# MP3.net
KiCad netlist of a schematic drawn in Altium Designer
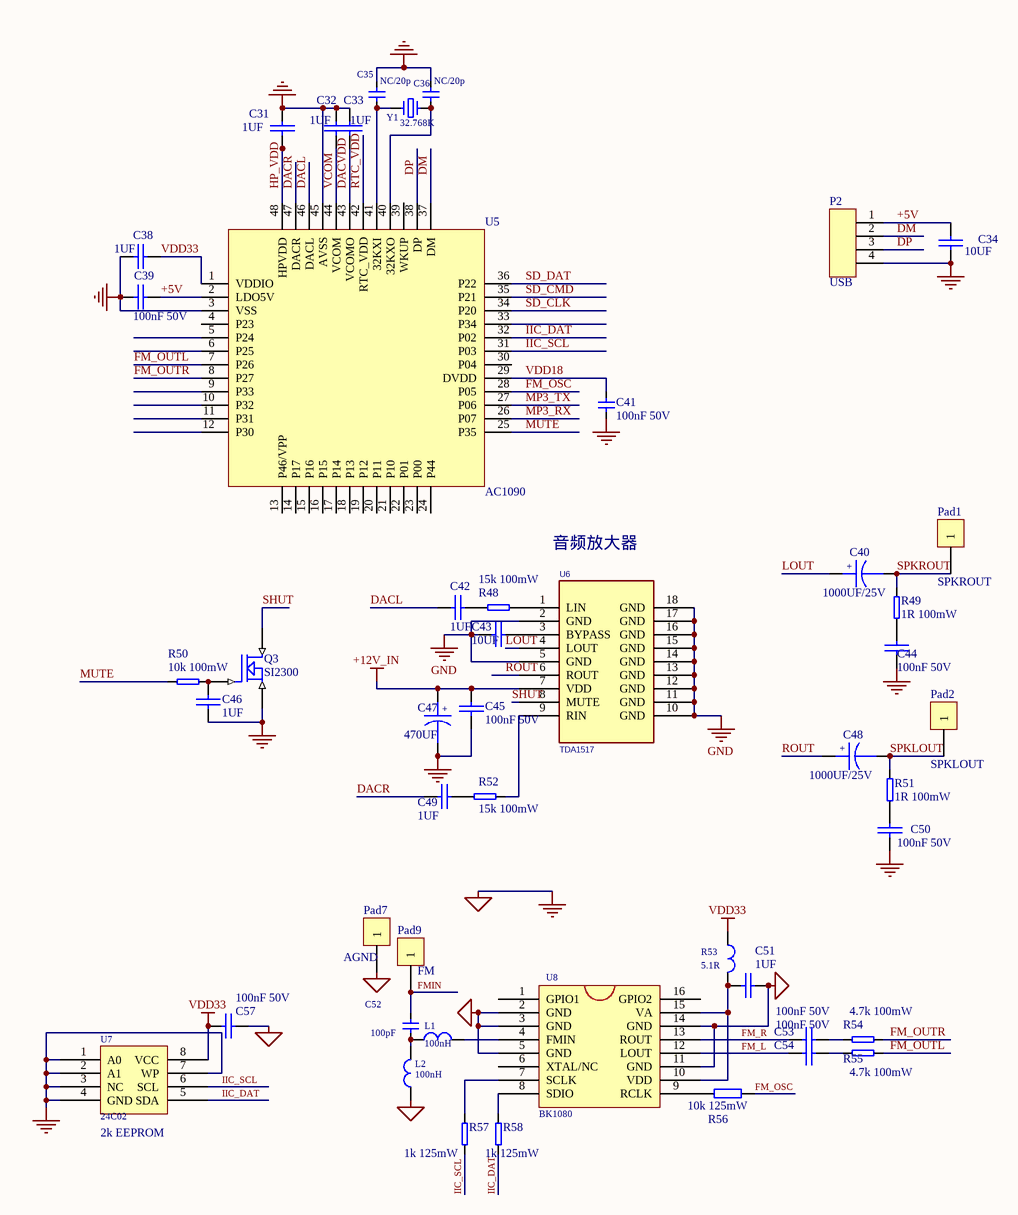
[diagram p0: MP3.SchDoc]

(export (version "E")
  (design (tool "Eeschema 10.0.6"))
  (components
    (comp (ref "C31")
      (value "1UF")
      (footprint "0805")
      (description "Capacitor")
      (libsource (lib "*") (part "CAP"))
    )
    (comp (ref "C32")
      (value "1UF")
      (footprint "0805")
      (description "Capacitor")
      (libsource (lib "*") (part "CAP"))
    )
    (comp (ref "C33")
      (value "1UF")
      (footprint "0805")
      (description "Capacitor")
      (libsource (lib "*") (part "CAP"))
    )
    (comp (ref "C34")
      (value "10UF")
      (footprint "0805")
      (description "Capacitor")
      (libsource (lib "*") (part "CAP"))
    )
    (comp (ref "C35")
      (value "NC/20p")
      (footprint "0603")
      (description "Capacitor")
      (libsource (lib "") (part "CAP_1"))
    )
    (comp (ref "C36")
      (value "NC/20p")
      (footprint "0603")
      (description "Capacitor")
      (libsource (lib "") (part "CAP_1"))
    )
    (comp (ref "C38")
      (value "1UF")
      (footprint "0805")
      (description "Capacitor")
      (libsource (lib "*") (part "CAP"))
    )
    (comp (ref "C39")
      (value "100nF 50V")
      (footprint "0805")
      (description "Capacitor")
      (libsource (lib "") (part "CAP_3"))
    )
    (comp (ref "C40")
      (value "1000UF/25V")
      (footprint "RB.2.4")
      (description "Capacitor")
      (libsource (lib "*") (part "CAPACITOR POL"))
    )
    (comp (ref "C41")
      (value "100nF 50V")
      (footprint "0603")
      (description "Capacitor")
      (libsource (lib "") (part "CAP_1"))
    )
    (comp (ref "C42")
      (value "1UF")
      (footprint "0805")
      (description "Capacitor")
      (libsource (lib "*") (part "CAP"))
    )
    (comp (ref "C43")
      (value "10UF")
      (footprint "0805")
      (description "Capacitor")
      (libsource (lib "*") (part "CAP_1"))
    )
    (comp (ref "C44")
      (value "100nF 50V")
      (footprint "0805")
      (description "Capacitor")
      (libsource (lib "") (part "CAP_3"))
    )
    (comp (ref "C45")
      (value "100nF 50V")
      (footprint "0805")
      (description "Capacitor")
      (libsource (lib "*") (part "CAP"))
    )
    (comp (ref "C46")
      (value "1UF")
      (footprint "0805")
      (description "Capacitor")
      (libsource (lib "*") (part "CAP"))
    )
    (comp (ref "C47")
      (value "470UF")
      (footprint "RB.2/.4")
      (description "Capacitor")
      (libsource (lib "*") (part "CAPACITOR POL"))
    )
    (comp (ref "C48")
      (value "1000UF/25V")
      (footprint "RB.2.4")
      (description "Capacitor")
      (libsource (lib "*") (part "CAPACITOR POL"))
    )
    (comp (ref "C49")
      (value "1UF")
      (footprint "0805")
      (description "Capacitor")
      (libsource (lib "*") (part "CAP"))
    )
    (comp (ref "C50")
      (value "100nF 50V")
      (footprint "0805")
      (description "Capacitor")
      (libsource (lib "") (part "CAP_3"))
    )
    (comp (ref "C51")
      (value "1UF")
      (footprint "0805")
      (description "Capacitor")
      (libsource (lib "*") (part "CAP"))
    )
    (comp (ref "C52")
      (value "100pF")
      (footprint "0603")
      (description "Capacitor")
      (libsource (lib "") (part "CAP_2"))
    )
    (comp (ref "C53")
      (value "100nF 50V")
      (footprint "0805")
      (description "Capacitor")
      (libsource (lib "*") (part "CAP"))
    )
    (comp (ref "C54")
      (value "100nF 50V")
      (footprint "0805")
      (description "Capacitor")
      (libsource (lib "*") (part "CAP"))
    )
    (comp (ref "C57")
      (value "100nF 50V")
      (footprint "0805")
      (description "Capacitor")
      (libsource (lib "*") (part "CAP"))
    )
    (comp (ref "L1") (value "100nH") (footprint "0603") (libsource (lib "*") (part "INDUCTOR")))
    (comp (ref "L2") (value "100nH") (footprint "0603") (libsource (lib "*") (part "INDUCTOR")))
    (comp (ref "P2") (value "USB") (footprint "SIP4") (libsource (lib "whlSCHLIB") (part "CON4")))
    (comp (ref "Pad1")
      (value "SPKROUT")
      (footprint "PAD")
      (description "Connector")
      (libsource (lib "*") (part "CON1"))
    )
    (comp (ref "Pad2")
      (value "SPKLOUT")
      (footprint "PAD")
      (description "Connector")
      (libsource (lib "*") (part "CON1"))
    )
    (comp (ref "Pad7")
      (value "AGND")
      (footprint "PAD")
      (description "Connector")
      (libsource (lib "*") (part "CON1"))
    )
    (comp (ref "Pad9")
      (value "FM")
      (footprint "PAD")
      (description "Connector")
      (libsource (lib "*") (part "CON1"))
    )
    (comp (ref "Q3") (value "SI2300") (footprint "SOT-23") (libsource (lib "*") (part "MOSFET N")))
    (comp (ref "R48") (value "15k 100mW") (footprint "0603") (libsource (lib "*") (part "RES2_1")))
    (comp (ref "R49") (value "1R 100mW") (footprint "0603") (libsource (lib "*") (part "RES2_1")))
    (comp (ref "R50") (value "10k 100mW") (footprint "0603") (libsource (lib "*") (part "RES2_1")))
    (comp (ref "R51") (value "1R 100mW") (footprint "0603") (libsource (lib "*") (part "RES2_1")))
    (comp (ref "R52") (value "15k 100mW") (footprint "0603") (libsource (lib "*") (part "RES2_1")))
    (comp (ref "R53") (value "5.1R") (footprint "0603") (libsource (lib "*") (part "INDUCTOR")))
    (comp (ref "R54") (value "4.7k 100mW") (footprint "0603") (libsource (lib "*") (part "RES2_1")))
    (comp (ref "R55") (value "4.7k 100mW") (footprint "0603") (libsource (lib "*") (part "RES2_1")))
    (comp (ref "R56") (value "10k 125mW") (footprint "0805") (libsource (lib "whlSCHLIB") (part "WHLRES")))
    (comp (ref "R57") (value "1k 125mW") (footprint "0805") (libsource (lib "*") (part "RES2_1")))
    (comp (ref "R58") (value "1k 125mW") (footprint "0805") (libsource (lib "*") (part "RES2_1")))
    (comp (ref "U5") (value "AC1090") (footprint "TQFP48 7X7") (libsource (lib "*") (part "AC1090")))
    (comp (ref "U6") (value "TDA1517") (footprint "DIP18") (libsource (lib "QX-T9") (part "74HC245_0")))
    (comp (ref "U7") (value "24C02") (footprint "SO-8") (libsource (lib "*") (part "EEPROM-8")))
    (comp (ref "U8") (value "BK1080") (footprint "SOP-16") (libsource (lib "*") (part "BK1080")))
    (comp (ref "Y1") (value "32.768K") (footprint "Cry3215") (libsource (lib "*") (part "CRYSTAL")))
  )
  (nets
    (net (code "1") (name "+12V_IN") (class "Default")
      (node (ref "C45") (pin "2") (pinfunction "2_2") (pintype "passive"))
      (node (ref "C47") (pin "1") (pinfunction "1_1") (pintype "passive"))
      (node (ref "U6") (pin "7") (pinfunction "VDD_7") (pintype "passive"))
    )
    (net (code "2") (name "/+5V") (class "Default")
      (node (ref "C34") (pin "1") (pinfunction "1_1") (pintype "passive"))
      (node (ref "C39") (pin "2") (pinfunction "2_2") (pintype "passive"))
      (node (ref "P2") (pin "1") (pintype "passive"))
      (node (ref "U5") (pin "2") (pinfunction "LDO5V_2") (pintype "passive"))
    )
    (net (code "3") (name "/DACL") (class "Default")
      (node (ref "C42") (pin "2") (pinfunction "2_2") (pintype "passive"))
      (node (ref "U5") (pin "46") (pinfunction "DACL_46") (pintype "passive"))
    )
    (net (code "4") (name "/DACR") (class "Default")
      (node (ref "C49") (pin "2") (pinfunction "2_2") (pintype "passive"))
      (node (ref "U5") (pin "47") (pinfunction "DACR_47") (pintype "passive"))
    )
    (net (code "5") (name "/DACVDD") (class "Default")
      (node (ref "C33") (pin "2") (pinfunction "2_2") (pintype "passive"))
      (node (ref "U5") (pin "43") (pinfunction "VCOMO_43") (pintype "passive"))
    )
    (net (code "6") (name "/DM") (class "Default")
      (node (ref "P2") (pin "2") (pintype "passive"))
      (node (ref "U5") (pin "37") (pinfunction "DM_37") (pintype "passive"))
    )
    (net (code "7") (name "/DP") (class "Default")
      (node (ref "P2") (pin "3") (pintype "passive"))
      (node (ref "U5") (pin "38") (pinfunction "DP_38") (pintype "passive"))
    )
    (net (code "8") (name "/FMIN") (class "Default")
      (node (ref "C52") (pin "1") (pinfunction "1_1") (pintype "passive"))
      (node (ref "Pad9") (pin "1") (pinfunction "1_1") (pintype "passive"))
    )
    (net (code "9") (name "/FM_L") (class "Default")
      (node (ref "C54") (pin "1") (pinfunction "1_1") (pintype "passive"))
      (node (ref "U8") (pin "12") (pinfunction "LOUT_12") (pintype "passive"))
    )
    (net (code "10") (name "/FM_OSC") (class "Default")
      (node (ref "R56") (pin "1") (pinfunction "1_1") (pintype "passive"))
      (node (ref "U5") (pin "28") (pinfunction "P05_28") (pintype "passive"))
    )
    (net (code "11") (name "/FM_OUTL") (class "Default")
      (node (ref "R55") (pin "2") (pinfunction "2_2") (pintype "passive"))
      (node (ref "U5") (pin "7") (pinfunction "P26_7") (pintype "passive"))
    )
    (net (code "12") (name "/FM_OUTR") (class "Default")
      (node (ref "R54") (pin "2") (pinfunction "2_2") (pintype "passive"))
      (node (ref "U5") (pin "8") (pinfunction "P27_8") (pintype "passive"))
    )
    (net (code "13") (name "/FM_R") (class "Default")
      (node (ref "C53") (pin "1") (pinfunction "1_1") (pintype "passive"))
      (node (ref "U8") (pin "13") (pinfunction "ROUT_13") (pintype "passive"))
    )
    (net (code "14") (name "/HP_VDD") (class "Default")
      (node (ref "C31") (pin "2") (pinfunction "2_2") (pintype "passive"))
      (node (ref "U5") (pin "48") (pinfunction "HPVDD_48") (pintype "passive"))
    )
    (net (code "15") (name "/IIC_DAT") (class "Default")
      (node (ref "R58") (pin "1") (pinfunction "1_1") (pintype "passive"))
      (node (ref "U5") (pin "32") (pinfunction "P02_32") (pintype "passive"))
      (node (ref "U7") (pin "5") (pinfunction "SDA_5") (pintype "passive"))
    )
    (net (code "16") (name "/IIC_SCL") (class "Default")
      (node (ref "R57") (pin "1") (pinfunction "1_1") (pintype "passive"))
      (node (ref "U5") (pin "31") (pinfunction "P03_31") (pintype "passive"))
      (node (ref "U7") (pin "6") (pinfunction "SCL_6") (pintype "passive"))
    )
    (net (code "17") (name "/LOUT") (class "Default")
      (node (ref "C40") (pin "1") (pinfunction "1_1") (pintype "passive"))
      (node (ref "U6") (pin "4") (pinfunction "LOUT_4") (pintype "passive"))
    )
    (net (code "18") (name "/MP3_RX") (class "Default")
      (node (ref "U5") (pin "26") (pinfunction "P07_26") (pintype "passive"))
    )
    (net (code "19") (name "/MP3_TX") (class "Default")
      (node (ref "U5") (pin "27") (pinfunction "P06_27") (pintype "passive"))
    )
    (net (code "20") (name "/MUTE") (class "Default")
      (node (ref "R50") (pin "1") (pinfunction "1_1") (pintype "passive"))
      (node (ref "U5") (pin "25") (pinfunction "P35_25") (pintype "passive"))
    )
    (net (code "21") (name "/ROUT") (class "Default")
      (node (ref "C48") (pin "1") (pinfunction "1_1") (pintype "passive"))
      (node (ref "U6") (pin "6") (pinfunction "ROUT_6") (pintype "passive"))
    )
    (net (code "22") (name "/RTC_VDD") (class "Default")
      (node (ref "U5") (pin "42") (pinfunction "RTC_VDD_42") (pintype "passive"))
    )
    (net (code "23") (name "/SD_CLK") (class "Default")
      (node (ref "U5") (pin "34") (pinfunction "P20_34") (pintype "passive"))
    )
    (net (code "24") (name "/SD_CMD") (class "Default")
      (node (ref "U5") (pin "35") (pinfunction "P21_35") (pintype "passive"))
    )
    (net (code "25") (name "/SD_DAT") (class "Default")
      (node (ref "U5") (pin "36") (pinfunction "P22_36") (pintype "passive"))
    )
    (net (code "26") (name "/SHUT") (class "Default")
      (node (ref "Q3") (pin "2") (pinfunction "D_2") (pintype "input"))
      (node (ref "U6") (pin "8") (pinfunction "MUTE_8") (pintype "passive"))
    )
    (net (code "27") (name "/SPKLOUT") (class "Default")
      (node (ref "C48") (pin "2") (pinfunction "2_2") (pintype "passive"))
      (node (ref "Pad2") (pin "1") (pinfunction "1_1") (pintype "passive"))
      (node (ref "R51") (pin "2") (pinfunction "2_2") (pintype "passive"))
    )
    (net (code "28") (name "/SPKROUT") (class "Default")
      (node (ref "C40") (pin "2") (pinfunction "2_2") (pintype "passive"))
      (node (ref "Pad1") (pin "1") (pinfunction "1_1") (pintype "passive"))
      (node (ref "R49") (pin "2") (pinfunction "2_2") (pintype "passive"))
    )
    (net (code "29") (name "/VCOM") (class "Default")
      (node (ref "C32") (pin "2") (pinfunction "2_2") (pintype "passive"))
      (node (ref "U5") (pin "44") (pinfunction "VCOM_44") (pintype "passive"))
    )
    (net (code "30") (name "/VDD18") (class "Default")
      (node (ref "C41") (pin "1") (pinfunction "1_1") (pintype "passive"))
      (node (ref "U5") (pin "29") (pinfunction "DVDD_29") (pintype "passive"))
    )
    (net (code "31") (name "AGND") (class "Default")
      (node (ref "C31") (pin "1") (pinfunction "1_1") (pintype "passive"))
      (node (ref "C32") (pin "1") (pinfunction "1_1") (pintype "passive"))
      (node (ref "C33") (pin "1") (pinfunction "1_1") (pintype "passive"))
      (node (ref "C34") (pin "2") (pinfunction "2_2") (pintype "passive"))
      (node (ref "C35") (pin "2") (pinfunction "2_2") (pintype "passive"))
      (node (ref "C36") (pin "2") (pinfunction "2_2") (pintype "passive"))
      (node (ref "C38") (pin "2") (pinfunction "2_2") (pintype "passive"))
      (node (ref "C39") (pin "1") (pinfunction "1_1") (pintype "passive"))
      (node (ref "C41") (pin "2") (pinfunction "2_2") (pintype "passive"))
      (node (ref "C43") (pin "1") (pinfunction "1_1") (pintype "passive"))
      (node (ref "C44") (pin "2") (pinfunction "2_2") (pintype "passive"))
      (node (ref "C45") (pin "1") (pinfunction "1_1") (pintype "passive"))
      (node (ref "C46") (pin "1") (pinfunction "1_1") (pintype "passive"))
      (node (ref "C47") (pin "2") (pinfunction "2_2") (pintype "passive"))
      (node (ref "C50") (pin "2") (pinfunction "2_2") (pintype "passive"))
      (node (ref "C51") (pin "1") (pinfunction "1_1") (pintype "passive"))
      (node (ref "C57") (pin "2") (pinfunction "2_2") (pintype "passive"))
      (node (ref "L2") (pin "1") (pinfunction "1_1") (pintype "passive"))
      (node (ref "P2") (pin "4") (pintype "passive"))
      (node (ref "Pad7") (pin "1") (pinfunction "1_1") (pintype "passive"))
      (node (ref "Q3") (pin "3") (pinfunction "S_3") (pintype "input"))
      (node (ref "U5") (pin "3") (pinfunction "VSS_3") (pintype "passive"))
      (node (ref "U5") (pin "45") (pinfunction "AVSS_45") (pintype "passive"))
      (node (ref "U6") (pin "10") (pinfunction "GND_10") (pintype "passive"))
      (node (ref "U6") (pin "11") (pinfunction "GND_11") (pintype "passive"))
      (node (ref "U6") (pin "12") (pinfunction "GND_12") (pintype "passive"))
      (node (ref "U6") (pin "13") (pinfunction "GND_13") (pintype "passive"))
      (node (ref "U6") (pin "14") (pinfunction "GND_14") (pintype "passive"))
      (node (ref "U6") (pin "15") (pinfunction "GND_15") (pintype "passive"))
      (node (ref "U6") (pin "16") (pinfunction "GND_16") (pintype "passive"))
      (node (ref "U6") (pin "17") (pinfunction "GND_17") (pintype "passive"))
      (node (ref "U6") (pin "18") (pinfunction "GND_18") (pintype "passive"))
      (node (ref "U6") (pin "2") (pinfunction "GND_2") (pintype "passive"))
      (node (ref "U6") (pin "5") (pinfunction "GND_5") (pintype "passive"))
      (node (ref "U7") (pin "1") (pinfunction "A0_1") (pintype "passive"))
      (node (ref "U7") (pin "2") (pinfunction "A1_2") (pintype "passive"))
      (node (ref "U7") (pin "3") (pinfunction "NC_3") (pintype "passive"))
      (node (ref "U7") (pin "4") (pinfunction "GND_4") (pintype "passive"))
      (node (ref "U7") (pin "7") (pinfunction "WP_7") (pintype "passive"))
      (node (ref "U8") (pin "11") (pinfunction "GND_11") (pintype "passive"))
      (node (ref "U8") (pin "14") (pinfunction "GND_14") (pintype "passive"))
      (node (ref "U8") (pin "2") (pinfunction "GND_2") (pintype "passive"))
      (node (ref "U8") (pin "3") (pinfunction "GND_3") (pintype "passive"))
      (node (ref "U8") (pin "5") (pinfunction "GND_5") (pintype "passive"))
    )
    (net (code "32") (name "Net-(C42-Pad1)") (class "Default")
      (node (ref "C42") (pin "1") (pinfunction "1_1") (pintype "passive"))
      (node (ref "R48") (pin "1") (pinfunction "1_1") (pintype "passive"))
    )
    (net (code "33") (name "Net-(C44-Pad1)") (class "Default")
      (node (ref "C44") (pin "1") (pinfunction "1_1") (pintype "passive"))
      (node (ref "R49") (pin "1") (pinfunction "1_1") (pintype "passive"))
    )
    (net (code "34") (name "Net-(C49-Pad1)") (class "Default")
      (node (ref "C49") (pin "1") (pinfunction "1_1") (pintype "passive"))
      (node (ref "R52") (pin "1") (pinfunction "1_1") (pintype "passive"))
    )
    (net (code "35") (name "Net-(C50-Pad1)") (class "Default")
      (node (ref "C50") (pin "1") (pinfunction "1_1") (pintype "passive"))
      (node (ref "R51") (pin "1") (pinfunction "1_1") (pintype "passive"))
    )
    (net (code "36") (name "Net-(C52-Pad2)") (class "Default")
      (node (ref "C52") (pin "2") (pinfunction "2_2") (pintype "passive"))
      (node (ref "L1") (pin "1") (pinfunction "1_1") (pintype "passive"))
      (node (ref "L2") (pin "2") (pinfunction "2_2") (pintype "passive"))
    )
    (net (code "37") (name "Net-(C53-Pad2)") (class "Default")
      (node (ref "C53") (pin "2") (pinfunction "2_2") (pintype "passive"))
      (node (ref "R54") (pin "1") (pinfunction "1_1") (pintype "passive"))
    )
    (net (code "38") (name "Net-(C54-Pad2)") (class "Default")
      (node (ref "C54") (pin "2") (pinfunction "2_2") (pintype "passive"))
      (node (ref "R55") (pin "1") (pinfunction "1_1") (pintype "passive"))
    )
    (net (code "39") (name "Net-(Q3-G)") (class "Default")
      (node (ref "C46") (pin "2") (pinfunction "2_2") (pintype "passive"))
      (node (ref "Q3") (pin "1") (pinfunction "G_1") (pintype "input"))
      (node (ref "R50") (pin "2") (pinfunction "2_2") (pintype "passive"))
    )
    (net (code "40") (name "Net-(U5-32KXI)") (class "Default")
      (node (ref "C35") (pin "1") (pinfunction "1_1") (pintype "passive"))
      (node (ref "U5") (pin "41") (pinfunction "32KXI_41") (pintype "passive"))
      (node (ref "Y1") (pin "2") (pinfunction "2_2") (pintype "passive"))
    )
    (net (code "41") (name "Net-(U5-32KXO)") (class "Default")
      (node (ref "C36") (pin "1") (pinfunction "1_1") (pintype "passive"))
      (node (ref "U5") (pin "40") (pinfunction "32KXO_40") (pintype "passive"))
      (node (ref "Y1") (pin "1") (pinfunction "1_1") (pintype "passive"))
    )
    (net (code "42") (name "Net-(U6-BYPASS)") (class "Default")
      (node (ref "C43") (pin "2") (pinfunction "2_2") (pintype "passive"))
      (node (ref "U6") (pin "3") (pinfunction "BYPASS_3") (pintype "passive"))
    )
    (net (code "43") (name "Net-(U6-LIN)") (class "Default")
      (node (ref "R48") (pin "2") (pinfunction "2_2") (pintype "passive"))
      (node (ref "U6") (pin "1") (pinfunction "LIN_1") (pintype "passive"))
    )
    (net (code "44") (name "Net-(U6-RIN)") (class "Default")
      (node (ref "R52") (pin "2") (pinfunction "2_2") (pintype "passive"))
      (node (ref "U6") (pin "9") (pinfunction "RIN_9") (pintype "passive"))
    )
    (net (code "45") (name "Net-(U8-FMIN)") (class "Default")
      (node (ref "L1") (pin "2") (pinfunction "2_2") (pintype "passive"))
      (node (ref "U8") (pin "4") (pinfunction "FMIN_4") (pintype "passive"))
    )
    (net (code "46") (name "Net-(U8-RCLK)") (class "Default")
      (node (ref "R56") (pin "2") (pinfunction "2_2") (pintype "passive"))
      (node (ref "U8") (pin "9") (pinfunction "RCLK_9") (pintype "passive"))
    )
    (net (code "47") (name "Net-(U8-SCLK)") (class "Default")
      (node (ref "R57") (pin "2") (pinfunction "2_2") (pintype "passive"))
      (node (ref "U8") (pin "7") (pinfunction "SCLK_7") (pintype "passive"))
    )
    (net (code "48") (name "Net-(U8-SDIO)") (class "Default")
      (node (ref "R58") (pin "2") (pinfunction "2_2") (pintype "passive"))
      (node (ref "U8") (pin "8") (pinfunction "SDIO_8") (pintype "passive"))
    )
    (net (code "49") (name "Net-(U8-VA)") (class "Default")
      (node (ref "C51") (pin "2") (pinfunction "2_2") (pintype "passive"))
      (node (ref "R53") (pin "2") (pinfunction "2_2") (pintype "passive"))
      (node (ref "U8") (pin "10") (pinfunction "VDD_10") (pintype "passive"))
      (node (ref "U8") (pin "15") (pinfunction "VA_15") (pintype "passive"))
    )
    (net (code "50") (name "VDD33") (class "Default")
      (node (ref "C38") (pin "1") (pinfunction "1_1") (pintype "passive"))
      (node (ref "C57") (pin "1") (pinfunction "1_1") (pintype "passive"))
      (node (ref "R53") (pin "1") (pinfunction "1_1") (pintype "passive"))
      (node (ref "U5") (pin "1") (pinfunction "VDDIO_1") (pintype "passive"))
      (node (ref "U7") (pin "8") (pinfunction "VCC_8") (pintype "passive"))
    )
    (net (code "51") (name "unconnected-(U5-P00-Pad23)") (class "Default")
      (node (ref "U5") (pin "23") (pinfunction "P00_23") (pintype "passive"))
    )
    (net (code "52") (name "unconnected-(U5-P01-Pad22)") (class "Default")
      (node (ref "U5") (pin "22") (pinfunction "P01_22") (pintype "passive"))
    )
    (net (code "53") (name "unconnected-(U5-P04-Pad30)") (class "Default")
      (node (ref "U5") (pin "30") (pinfunction "P04_30") (pintype "passive"))
    )
    (net (code "54") (name "unconnected-(U5-P10-Pad21)") (class "Default")
      (node (ref "U5") (pin "21") (pinfunction "P10_21") (pintype "passive"))
    )
    (net (code "55") (name "unconnected-(U5-P11-Pad20)") (class "Default")
      (node (ref "U5") (pin "20") (pinfunction "P11_20") (pintype "passive"))
    )
    (net (code "56") (name "unconnected-(U5-P12-Pad19)") (class "Default")
      (node (ref "U5") (pin "19") (pinfunction "P12_19") (pintype "passive"))
    )
    (net (code "57") (name "unconnected-(U5-P13-Pad18)") (class "Default")
      (node (ref "U5") (pin "18") (pinfunction "P13_18") (pintype "passive"))
    )
    (net (code "58") (name "unconnected-(U5-P14-Pad17)") (class "Default")
      (node (ref "U5") (pin "17") (pinfunction "P14_17") (pintype "passive"))
    )
    (net (code "59") (name "unconnected-(U5-P15-Pad16)") (class "Default")
      (node (ref "U5") (pin "16") (pinfunction "P15_16") (pintype "passive"))
    )
    (net (code "60") (name "unconnected-(U5-P16-Pad15)") (class "Default")
      (node (ref "U5") (pin "15") (pinfunction "P16_15") (pintype "passive"))
    )
    (net (code "61") (name "unconnected-(U5-P17-Pad14)") (class "Default")
      (node (ref "U5") (pin "14") (pinfunction "P17_14") (pintype "passive"))
    )
    (net (code "62") (name "unconnected-(U5-P23-Pad4)") (class "Default")
      (node (ref "U5") (pin "4") (pinfunction "P23_4") (pintype "passive"))
    )
    (net (code "63") (name "unconnected-(U5-P24-Pad5)") (class "Default")
      (node (ref "U5") (pin "5") (pinfunction "P24_5") (pintype "passive"))
    )
    (net (code "64") (name "unconnected-(U5-P25-Pad6)") (class "Default")
      (node (ref "U5") (pin "6") (pinfunction "P25_6") (pintype "passive"))
    )
    (net (code "65") (name "unconnected-(U5-P30-Pad12)") (class "Default")
      (node (ref "U5") (pin "12") (pinfunction "P30_12") (pintype "passive"))
    )
    (net (code "66") (name "unconnected-(U5-P31-Pad11)") (class "Default")
      (node (ref "U5") (pin "11") (pinfunction "P31_11") (pintype "passive"))
    )
    (net (code "67") (name "unconnected-(U5-P32-Pad10)") (class "Default")
      (node (ref "U5") (pin "10") (pinfunction "P32_10") (pintype "passive"))
    )
    (net (code "68") (name "unconnected-(U5-P33-Pad9)") (class "Default")
      (node (ref "U5") (pin "9") (pinfunction "P33_9") (pintype "passive"))
    )
    (net (code "69") (name "unconnected-(U5-P34-Pad33)") (class "Default")
      (node (ref "U5") (pin "33") (pinfunction "P34_33") (pintype "passive"))
    )
    (net (code "70") (name "unconnected-(U5-P44-Pad24)") (class "Default")
      (node (ref "U5") (pin "24") (pinfunction "P44_24") (pintype "passive"))
    )
    (net (code "71") (name "unconnected-(U5-P46{slash}VPP-Pad13)") (class "Default")
      (node (ref "U5") (pin "13") (pinfunction "P46/VPP_13") (pintype "passive"))
    )
    (net (code "72") (name "unconnected-(U5-WKUP-Pad39)") (class "Default")
      (node (ref "U5") (pin "39") (pinfunction "WKUP_39") (pintype "passive"))
    )
    (net (code "73") (name "unconnected-(U8-GPIO1-Pad1)") (class "Default")
      (node (ref "U8") (pin "1") (pinfunction "GPIO1_1") (pintype "passive"))
    )
    (net (code "74") (name "unconnected-(U8-GPIO2-Pad16)") (class "Default")
      (node (ref "U8") (pin "16") (pinfunction "GPIO2_16") (pintype "passive"))
    )
    (net (code "75") (name "unconnected-(U8-XTAL{slash}NC-Pad6)") (class "Default")
      (node (ref "U8") (pin "6") (pinfunction "XTAL/NC_6") (pintype "passive"))
    )
  )
)
